# 4_periferals.net
KiCad netlist of a schematic drawn in Altium Designer
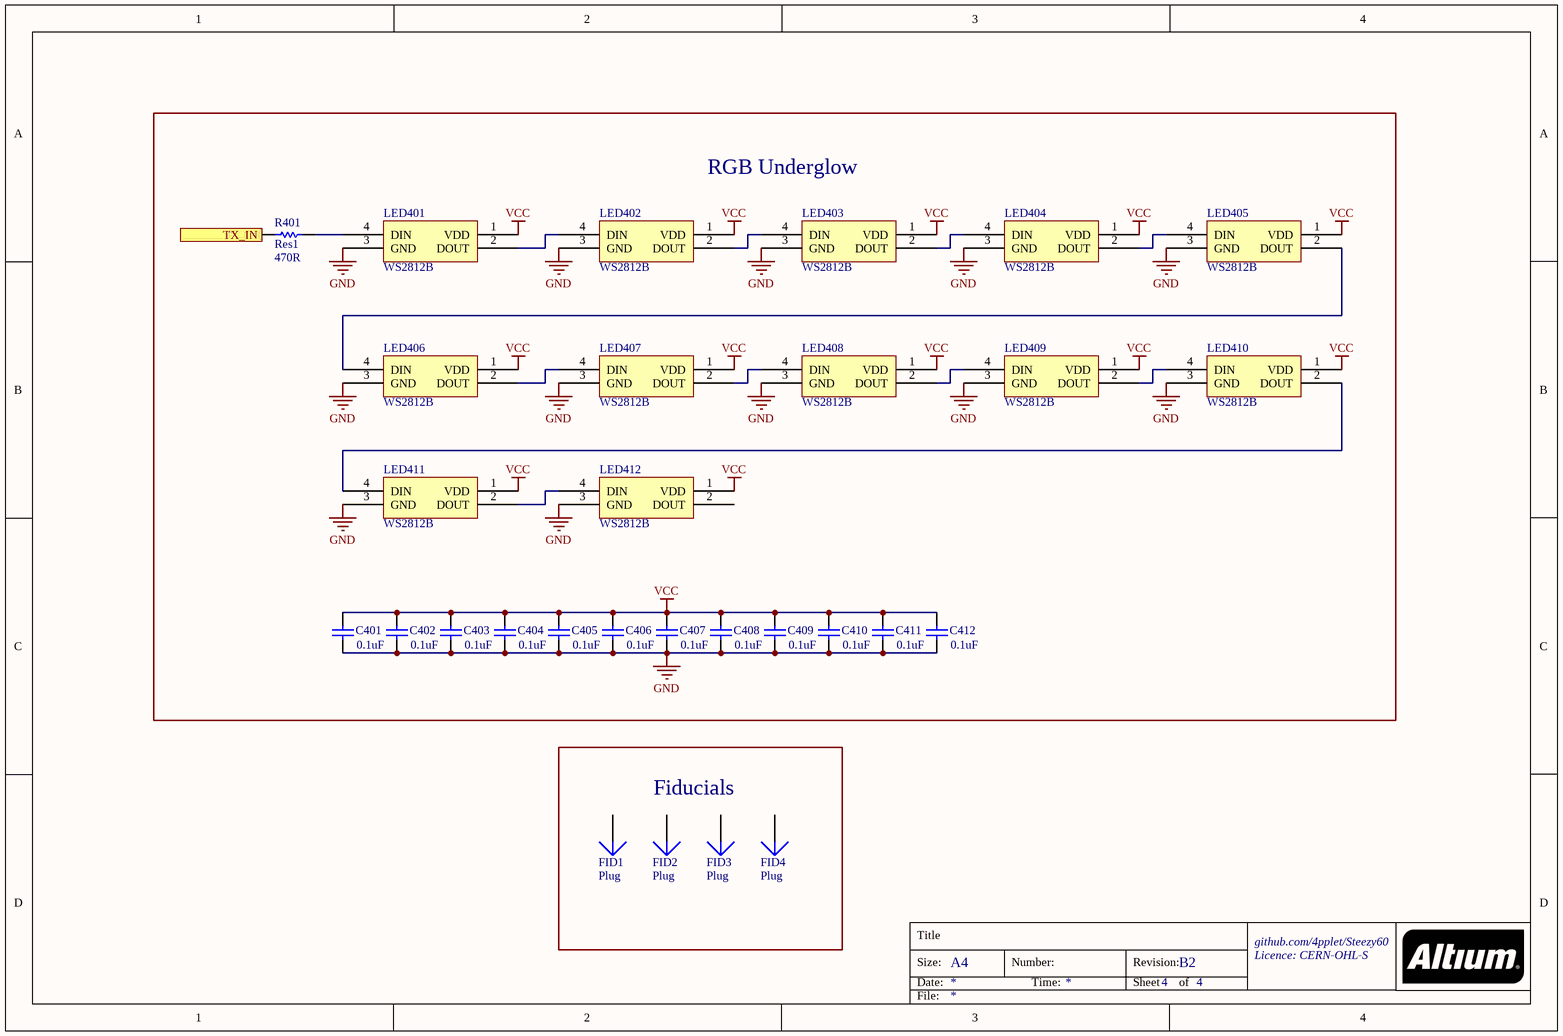
[diagram p0: 4_periferals.SchDoc]

(export (version "E")
  (design (tool "Eeschema 10.0.6"))
  (components
    (comp (ref "C401")
      (value "0.1uF")
      (footprint "C0603[1608]")
      (description "Capacitor")
      (fields (field (name "MFG") "KEMET") (field (name "LCSC PART #") "C14663"))
      (libsource (lib "Miscellaneous Devices") (part "Cap"))
    )
    (comp (ref "C402")
      (value "0.1uF")
      (footprint "C0603[1608]")
      (description "Capacitor")
      (fields (field (name "MFG") "KEMET") (field (name "LCSC PART #") "C14663"))
      (libsource (lib "Miscellaneous Devices") (part "Cap"))
    )
    (comp (ref "C403")
      (value "0.1uF")
      (footprint "C0603[1608]")
      (description "Capacitor")
      (fields (field (name "MFG") "KEMET") (field (name "LCSC PART #") "C14663"))
      (libsource (lib "Miscellaneous Devices") (part "Cap"))
    )
    (comp (ref "C404")
      (value "0.1uF")
      (footprint "C0603[1608]")
      (description "Capacitor")
      (fields (field (name "MFG") "KEMET") (field (name "LCSC PART #") "C14663"))
      (libsource (lib "Miscellaneous Devices") (part "Cap"))
    )
    (comp (ref "C405")
      (value "0.1uF")
      (footprint "C0603[1608]")
      (description "Capacitor")
      (fields (field (name "MFG") "KEMET") (field (name "LCSC PART #") "C14663"))
      (libsource (lib "Miscellaneous Devices") (part "Cap"))
    )
    (comp (ref "C406")
      (value "0.1uF")
      (footprint "C0603[1608]")
      (description "Capacitor")
      (fields (field (name "MFG") "KEMET") (field (name "LCSC PART #") "C14663"))
      (libsource (lib "Miscellaneous Devices") (part "Cap"))
    )
    (comp (ref "C407")
      (value "0.1uF")
      (footprint "C0603[1608]")
      (description "Capacitor")
      (fields (field (name "MFG") "KEMET") (field (name "LCSC PART #") "C14663"))
      (libsource (lib "Miscellaneous Devices") (part "Cap"))
    )
    (comp (ref "C408")
      (value "0.1uF")
      (footprint "C0603[1608]")
      (description "Capacitor")
      (fields (field (name "MFG") "KEMET") (field (name "LCSC PART #") "C14663"))
      (libsource (lib "Miscellaneous Devices") (part "Cap"))
    )
    (comp (ref "C409")
      (value "0.1uF")
      (footprint "C0603[1608]")
      (description "Capacitor")
      (fields (field (name "MFG") "KEMET") (field (name "LCSC PART #") "C14663"))
      (libsource (lib "Miscellaneous Devices") (part "Cap"))
    )
    (comp (ref "C410")
      (value "0.1uF")
      (footprint "C0603[1608]")
      (description "Capacitor")
      (fields (field (name "MFG") "KEMET") (field (name "LCSC PART #") "C14663"))
      (libsource (lib "Miscellaneous Devices") (part "Cap"))
    )
    (comp (ref "C411")
      (value "0.1uF")
      (footprint "C0603[1608]")
      (description "Capacitor")
      (fields (field (name "MFG") "KEMET") (field (name "LCSC PART #") "C14663"))
      (libsource (lib "Miscellaneous Devices") (part "Cap"))
    )
    (comp (ref "C412")
      (value "0.1uF")
      (footprint "C0603[1608]")
      (description "Capacitor")
      (fields (field (name "MFG") "KEMET") (field (name "LCSC PART #") "C14663"))
      (libsource (lib "Miscellaneous Devices") (part "Cap"))
    )
    (comp (ref "FID1")
      (value "Plug")
      (footprint "Fiducial_Nordic")
      (libsource (lib "Miscellaneous Connectors") (part "Plug"))
    )
    (comp (ref "FID2")
      (value "Plug")
      (footprint "Fiducial_Nordic")
      (libsource (lib "Miscellaneous Connectors") (part "Plug"))
    )
    (comp (ref "FID3")
      (value "Plug")
      (footprint "Fiducial_Nordic")
      (libsource (lib "Miscellaneous Connectors") (part "Plug"))
    )
    (comp (ref "FID4")
      (value "Plug")
      (footprint "Fiducial_Nordic")
      (libsource (lib "Miscellaneous Connectors") (part "Plug"))
    )
    (comp (ref "LED401")
      (value "WS2812B")
      (footprint "WS2812B - 2020")
      (fields (field (name "LCSC PART #") "C3646929") (field (name "MRF.PART") "XL-0807RGBC-WS2812B"))
      (libsource (lib "Keebs") (part "WS2812B"))
    )
    (comp (ref "LED402")
      (value "WS2812B")
      (footprint "WS2812B - 2020")
      (fields (field (name "LCSC PART #") "C3646929") (field (name "MRF.PART") "XL-0807RGBC-WS2812B"))
      (libsource (lib "Keebs") (part "WS2812B"))
    )
    (comp (ref "LED403")
      (value "WS2812B")
      (footprint "WS2812B - 2020")
      (fields (field (name "LCSC PART #") "C3646929") (field (name "MRF.PART") "XL-0807RGBC-WS2812B"))
      (libsource (lib "Keebs") (part "WS2812B"))
    )
    (comp (ref "LED404")
      (value "WS2812B")
      (footprint "WS2812B - 2020")
      (fields (field (name "LCSC PART #") "C3646929") (field (name "MRF.PART") "XL-0807RGBC-WS2812B"))
      (libsource (lib "Keebs") (part "WS2812B"))
    )
    (comp (ref "LED405")
      (value "WS2812B")
      (footprint "WS2812B - 2020")
      (fields (field (name "LCSC PART #") "C3646929") (field (name "MRF.PART") "XL-0807RGBC-WS2812B"))
      (libsource (lib "Keebs") (part "WS2812B"))
    )
    (comp (ref "LED406")
      (value "WS2812B")
      (footprint "WS2812B - 2020")
      (fields (field (name "LCSC PART #") "C3646929") (field (name "MRF.PART") "XL-0807RGBC-WS2812B"))
      (libsource (lib "Keebs") (part "WS2812B"))
    )
    (comp (ref "LED407")
      (value "WS2812B")
      (footprint "WS2812B - 2020")
      (fields (field (name "LCSC PART #") "C3646929") (field (name "MRF.PART") "XL-0807RGBC-WS2812B"))
      (libsource (lib "Keebs") (part "WS2812B"))
    )
    (comp (ref "LED408")
      (value "WS2812B")
      (footprint "WS2812B - 2020")
      (fields (field (name "LCSC PART #") "C3646929") (field (name "MRF.PART") "XL-0807RGBC-WS2812B"))
      (libsource (lib "Keebs") (part "WS2812B"))
    )
    (comp (ref "LED409")
      (value "WS2812B")
      (footprint "WS2812B - 2020")
      (fields (field (name "LCSC PART #") "C3646929") (field (name "MRF.PART") "XL-0807RGBC-WS2812B"))
      (libsource (lib "Keebs") (part "WS2812B"))
    )
    (comp (ref "LED410")
      (value "WS2812B")
      (footprint "WS2812B - 2020")
      (fields (field (name "LCSC PART #") "C3646929") (field (name "MRF.PART") "XL-0807RGBC-WS2812B"))
      (libsource (lib "Keebs") (part "WS2812B"))
    )
    (comp (ref "LED411")
      (value "WS2812B")
      (footprint "WS2812B - 2020")
      (fields (field (name "LCSC PART #") "C3646929") (field (name "MRF.PART") "XL-0807RGBC-WS2812B"))
      (libsource (lib "Keebs") (part "WS2812B"))
    )
    (comp (ref "LED412")
      (value "WS2812B")
      (footprint "WS2812B - 2020")
      (fields (field (name "LCSC PART #") "C3646929") (field (name "MRF.PART") "XL-0807RGBC-WS2812B"))
      (libsource (lib "Keebs") (part "WS2812B"))
    )
    (comp (ref "R401")
      (value "Res1")
      (footprint "R0603[1608]")
      (description "Resistor")
      (fields
        (field (name "ALTIUM_VALUE") "470R")
        (field (name "MFG") "Panasonic Electronic Components")
        (field (name "LCSC PART #") "C23179")
      )
      (libsource (lib "Miscellaneous Devices") (part "Res1"))
    )
  )
  (nets
    (net (code "1") (name "/TX_IN") (class "Default")
      (node (ref "R401") (pin "1") (pinfunction "1_1") (pintype "passive"))
    )
    (net (code "2") (name "GND") (class "Default")
      (node (ref "C401") (pin "1") (pinfunction "1_1") (pintype "passive"))
      (node (ref "C402") (pin "1") (pinfunction "1_1") (pintype "passive"))
      (node (ref "C403") (pin "1") (pinfunction "1_1") (pintype "passive"))
      (node (ref "C404") (pin "1") (pinfunction "1_1") (pintype "passive"))
      (node (ref "C405") (pin "1") (pinfunction "1_1") (pintype "passive"))
      (node (ref "C406") (pin "1") (pinfunction "1_1") (pintype "passive"))
      (node (ref "C407") (pin "1") (pinfunction "1_1") (pintype "passive"))
      (node (ref "C408") (pin "1") (pinfunction "1_1") (pintype "passive"))
      (node (ref "C409") (pin "1") (pinfunction "1_1") (pintype "passive"))
      (node (ref "C410") (pin "1") (pinfunction "1_1") (pintype "passive"))
      (node (ref "C411") (pin "1") (pinfunction "1_1") (pintype "passive"))
      (node (ref "C412") (pin "1") (pinfunction "1_1") (pintype "passive"))
      (node (ref "LED401") (pin "3") (pinfunction "GND_3") (pintype "passive"))
      (node (ref "LED402") (pin "3") (pinfunction "GND_3") (pintype "passive"))
      (node (ref "LED403") (pin "3") (pinfunction "GND_3") (pintype "passive"))
      (node (ref "LED404") (pin "3") (pinfunction "GND_3") (pintype "passive"))
      (node (ref "LED405") (pin "3") (pinfunction "GND_3") (pintype "passive"))
      (node (ref "LED406") (pin "3") (pinfunction "GND_3") (pintype "passive"))
      (node (ref "LED407") (pin "3") (pinfunction "GND_3") (pintype "passive"))
      (node (ref "LED408") (pin "3") (pinfunction "GND_3") (pintype "passive"))
      (node (ref "LED409") (pin "3") (pinfunction "GND_3") (pintype "passive"))
      (node (ref "LED410") (pin "3") (pinfunction "GND_3") (pintype "passive"))
      (node (ref "LED411") (pin "3") (pinfunction "GND_3") (pintype "passive"))
      (node (ref "LED412") (pin "3") (pinfunction "GND_3") (pintype "passive"))
    )
    (net (code "3") (name "Net-(LED401-DIN)") (class "Default")
      (node (ref "LED401") (pin "4") (pinfunction "DIN_4") (pintype "passive"))
      (node (ref "R401") (pin "2") (pinfunction "2_2") (pintype "passive"))
    )
    (net (code "4") (name "Net-(LED401-DOUT)") (class "Default")
      (node (ref "LED401") (pin "2") (pinfunction "DOUT_2") (pintype "passive"))
      (node (ref "LED402") (pin "4") (pinfunction "DIN_4") (pintype "passive"))
    )
    (net (code "5") (name "Net-(LED402-DOUT)") (class "Default")
      (node (ref "LED402") (pin "2") (pinfunction "DOUT_2") (pintype "passive"))
      (node (ref "LED403") (pin "4") (pinfunction "DIN_4") (pintype "passive"))
    )
    (net (code "6") (name "Net-(LED403-DOUT)") (class "Default")
      (node (ref "LED403") (pin "2") (pinfunction "DOUT_2") (pintype "passive"))
      (node (ref "LED404") (pin "4") (pinfunction "DIN_4") (pintype "passive"))
    )
    (net (code "7") (name "Net-(LED404-DOUT)") (class "Default")
      (node (ref "LED404") (pin "2") (pinfunction "DOUT_2") (pintype "passive"))
      (node (ref "LED405") (pin "4") (pinfunction "DIN_4") (pintype "passive"))
    )
    (net (code "8") (name "Net-(LED405-DOUT)") (class "Default")
      (node (ref "LED405") (pin "2") (pinfunction "DOUT_2") (pintype "passive"))
      (node (ref "LED406") (pin "4") (pinfunction "DIN_4") (pintype "passive"))
    )
    (net (code "9") (name "Net-(LED406-DOUT)") (class "Default")
      (node (ref "LED406") (pin "2") (pinfunction "DOUT_2") (pintype "passive"))
      (node (ref "LED407") (pin "4") (pinfunction "DIN_4") (pintype "passive"))
    )
    (net (code "10") (name "Net-(LED407-DOUT)") (class "Default")
      (node (ref "LED407") (pin "2") (pinfunction "DOUT_2") (pintype "passive"))
      (node (ref "LED408") (pin "4") (pinfunction "DIN_4") (pintype "passive"))
    )
    (net (code "11") (name "Net-(LED408-DOUT)") (class "Default")
      (node (ref "LED408") (pin "2") (pinfunction "DOUT_2") (pintype "passive"))
      (node (ref "LED409") (pin "4") (pinfunction "DIN_4") (pintype "passive"))
    )
    (net (code "12") (name "Net-(LED409-DOUT)") (class "Default")
      (node (ref "LED409") (pin "2") (pinfunction "DOUT_2") (pintype "passive"))
      (node (ref "LED410") (pin "4") (pinfunction "DIN_4") (pintype "passive"))
    )
    (net (code "13") (name "Net-(LED410-DOUT)") (class "Default")
      (node (ref "LED410") (pin "2") (pinfunction "DOUT_2") (pintype "passive"))
      (node (ref "LED411") (pin "4") (pinfunction "DIN_4") (pintype "passive"))
    )
    (net (code "14") (name "Net-(LED411-DOUT)") (class "Default")
      (node (ref "LED411") (pin "2") (pinfunction "DOUT_2") (pintype "passive"))
      (node (ref "LED412") (pin "4") (pinfunction "DIN_4") (pintype "passive"))
    )
    (net (code "15") (name "VCC") (class "Default")
      (node (ref "C401") (pin "2") (pinfunction "2_2") (pintype "passive"))
      (node (ref "C402") (pin "2") (pinfunction "2_2") (pintype "passive"))
      (node (ref "C403") (pin "2") (pinfunction "2_2") (pintype "passive"))
      (node (ref "C404") (pin "2") (pinfunction "2_2") (pintype "passive"))
      (node (ref "C405") (pin "2") (pinfunction "2_2") (pintype "passive"))
      (node (ref "C406") (pin "2") (pinfunction "2_2") (pintype "passive"))
      (node (ref "C407") (pin "2") (pinfunction "2_2") (pintype "passive"))
      (node (ref "C408") (pin "2") (pinfunction "2_2") (pintype "passive"))
      (node (ref "C409") (pin "2") (pinfunction "2_2") (pintype "passive"))
      (node (ref "C410") (pin "2") (pinfunction "2_2") (pintype "passive"))
      (node (ref "C411") (pin "2") (pinfunction "2_2") (pintype "passive"))
      (node (ref "C412") (pin "2") (pinfunction "2_2") (pintype "passive"))
      (node (ref "LED401") (pin "1") (pinfunction "VDD_1") (pintype "passive"))
      (node (ref "LED402") (pin "1") (pinfunction "VDD_1") (pintype "passive"))
      (node (ref "LED403") (pin "1") (pinfunction "VDD_1") (pintype "passive"))
      (node (ref "LED404") (pin "1") (pinfunction "VDD_1") (pintype "passive"))
      (node (ref "LED405") (pin "1") (pinfunction "VDD_1") (pintype "passive"))
      (node (ref "LED406") (pin "1") (pinfunction "VDD_1") (pintype "passive"))
      (node (ref "LED407") (pin "1") (pinfunction "VDD_1") (pintype "passive"))
      (node (ref "LED408") (pin "1") (pinfunction "VDD_1") (pintype "passive"))
      (node (ref "LED409") (pin "1") (pinfunction "VDD_1") (pintype "passive"))
      (node (ref "LED410") (pin "1") (pinfunction "VDD_1") (pintype "passive"))
      (node (ref "LED411") (pin "1") (pinfunction "VDD_1") (pintype "passive"))
      (node (ref "LED412") (pin "1") (pinfunction "VDD_1") (pintype "passive"))
    )
    (net (code "16") (name "unconnected-(FID1-Pad1)") (class "Default")
      (node (ref "FID1") (pin "1") (pinfunction "1_1") (pintype "passive"))
    )
    (net (code "17") (name "unconnected-(FID2-Pad1)") (class "Default")
      (node (ref "FID2") (pin "1") (pinfunction "1_1") (pintype "passive"))
    )
    (net (code "18") (name "unconnected-(FID3-Pad1)") (class "Default")
      (node (ref "FID3") (pin "1") (pinfunction "1_1") (pintype "passive"))
    )
    (net (code "19") (name "unconnected-(FID4-Pad1)") (class "Default")
      (node (ref "FID4") (pin "1") (pinfunction "1_1") (pintype "passive"))
    )
    (net (code "20") (name "unconnected-(LED412-DOUT-Pad2)") (class "Default")
      (node (ref "LED412") (pin "2") (pinfunction "DOUT_2") (pintype "passive"))
    )
  )
)
